# RS485.net
KiCad netlist of a schematic drawn in Altium Designer
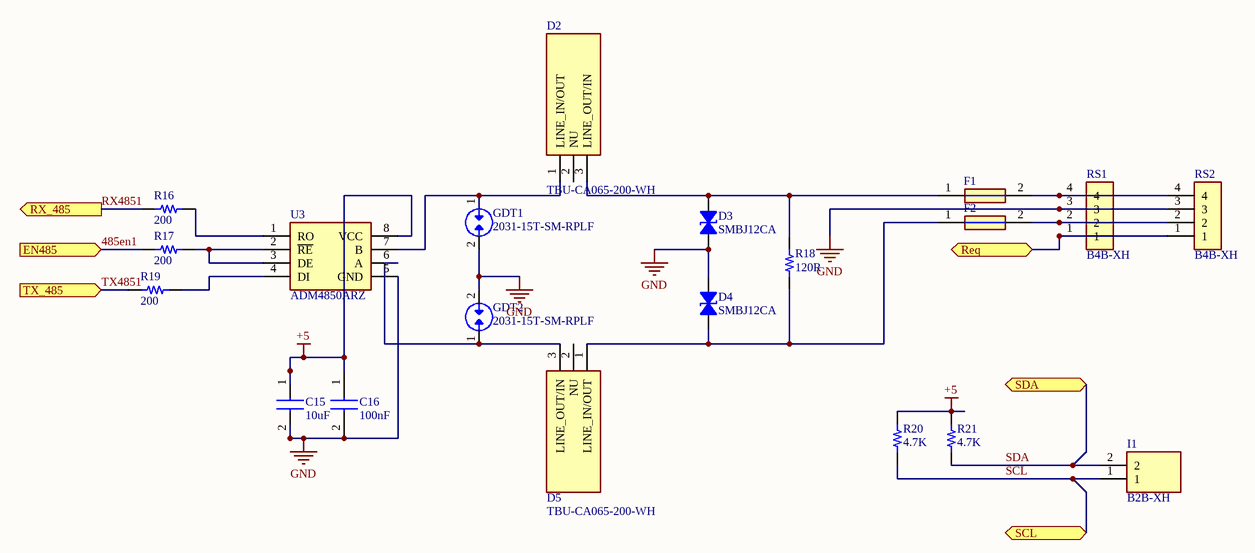
[diagram p0: RS485.SchDoc]

(export (version "E")
  (design (tool "Eeschema 10.0.6"))
  (components
    (comp (ref "C15")
      (value "10uF")
      (footprint "0603C")
      (description "CAP SMD 0603")
      (fields
        (field (name "MANUFACTURER_PART_NUMBER") "C1206C104Z5UACTU")
        (field (name "MOUSER PART NUMBER") "80-C1206C104Z5U")
      )
      (libsource (lib "*") (part "C1206C104Z5UACTU"))
    )
    (comp (ref "C16")
      (value "100nF")
      (footprint "0603C")
      (description "CAP SMD 0603")
      (fields
        (field (name "MANUFACTURER_PART_NUMBER") "C1206C104Z5UACTU")
        (field (name "MOUSER PART NUMBER") "80-C1206C104Z5U")
      )
      (libsource (lib "*") (part "C1206C104Z5UACTU"))
    )
    (comp (ref "D2")
      (value "TBU-CA065-200-WH")
      (footprint "TBUCA025050WH")
      (description "TVS Diode (Bi-directional)")
      (fields (field (name "MOUSER PART NUMBER") "652-TBU-CA065-200-WH"))
      (libsource (lib "") (part "TBU-CA065-200-WH_1"))
    )
    (comp (ref "D3")
      (value "SMBJ12CA")
      (footprint "DO214AA SMB")
      (description "TVS DIODE 12V 19.9V SMB")
      (fields (field (name "MANUFACTURER") "AVX Corporation"))
      (libsource (lib "Celestial Altium Library - altium_library") (part "Diode TVS"))
    )
    (comp (ref "D4")
      (value "SMBJ12CA")
      (footprint "DO214AA SMB")
      (description "TVS DIODE 12V 19.9V SMB")
      (fields (field (name "MANUFACTURER") "AVX Corporation"))
      (libsource (lib "Celestial Altium Library - altium_library") (part "Diode TVS"))
    )
    (comp (ref "D5")
      (value "TBU-CA065-200-WH")
      (footprint "TBUCA025050WH")
      (description "TVS Diode (Bi-directional)")
      (fields (field (name "MOUSER PART NUMBER") "652-TBU-CA065-200-WH"))
      (libsource (lib "*") (part "TBU-CA065-200-WH"))
    )
    (comp (ref "F1")
      (value "fuse 100mAmp")
      (footprint "1206 FUSE")
      (description "Fuse 1206")
      (fields (field (name "MANUFACTURER_PART_NUMBER") "1206SFS200F/63-2"))
      (libsource (lib "*") (part "1206SFS200F_63-2"))
    )
    (comp (ref "F2")
      (value "fuse 100mAmp")
      (footprint "1206 FUSE")
      (description "Fuse 1206")
      (fields (field (name "MANUFACTURER_PART_NUMBER") "1206SFS200F/63-2"))
      (libsource (lib "*") (part "1206SFS200F_63-2"))
    )
    (comp (ref "GDT1")
      (value "2031-15T-SM-RPLF")
      (footprint "TVS_2031-15T-SM-RPLF")
      (description "Gas Discharge Tube SMD")
      (libsource (lib "2031-15T-SM-RPLF") (part "2031-15T-SM-RPLF"))
    )
    (comp (ref "GDT2")
      (value "2031-15T-SM-RPLF")
      (footprint "TVS_2031-15T-SM-RPLF")
      (description "Gas Discharge Tube SMD")
      (libsource (lib "2031-15T-SM-RPLF") (part "2031-15T-SM-RPLF"))
    )
    (comp (ref "I1")
      (value "B2B-XH")
      (footprint "JST-B2B-XH")
      (description "XH 2pin standing")
      (libsource (lib "XHBBLIB") (part "B2B-XH"))
    )
    (comp (ref "R16")
      (value "200")
      (footprint "0603R")
      (description "RES SMD 0603")
      (fields (field (name "PART NUMBER") "CRCW080510K0JNEAIF") (field (name "MANUFACTURER") "Vishay Dale"))
      (libsource (lib "Celestial Altium Library - altium_library") (part "Resistor"))
    )
    (comp (ref "R17")
      (value "200")
      (footprint "0603R")
      (description "RES SMD 0603")
      (fields (field (name "PART NUMBER") "CRCW080510K0JNEAIF") (field (name "MANUFACTURER") "Vishay Dale"))
      (libsource (lib "Celestial Altium Library - altium_library") (part "Resistor"))
    )
    (comp (ref "R18")
      (value "120R")
      (footprint "0603R")
      (description "RES SMD 0603")
      (fields (field (name "PART NUMBER") "CRCW080510K0JNEAIF") (field (name "MANUFACTURER") "Vishay Dale"))
      (libsource (lib "Celestial Altium Library - altium_library") (part "Resistor"))
    )
    (comp (ref "R19")
      (value "200")
      (footprint "0603R")
      (description "RES SMD 0603")
      (fields (field (name "PART NUMBER") "CRCW080510K0JNEAIF") (field (name "MANUFACTURER") "Vishay Dale"))
      (libsource (lib "Celestial Altium Library - altium_library") (part "Resistor"))
    )
    (comp (ref "R20")
      (value "4.7K")
      (footprint "0603R")
      (description "RES SMD 0603")
      (fields (field (name "PART NUMBER") "CRCW080510K0JNEAIF") (field (name "MANUFACTURER") "Vishay Dale"))
      (libsource (lib "Celestial Altium Library - altium_library") (part "Resistor"))
    )
    (comp (ref "R21")
      (value "4.7K")
      (footprint "0603R")
      (description "RES SMD 0603")
      (fields (field (name "PART NUMBER") "CRCW080510K0JNEAIF") (field (name "MANUFACTURER") "Vishay Dale"))
      (libsource (lib "Celestial Altium Library - altium_library") (part "Resistor"))
    )
    (comp (ref "RS1")
      (value "B4B-XH")
      (footprint "JST-B4B-XH")
      (description "XH 4pin standing")
      (libsource (lib "XHBBLIB") (part "B4B-XH"))
    )
    (comp (ref "RS2")
      (value "B4B-XH")
      (footprint "JST-B4B-XH")
      (description "XH 4pin standing")
      (libsource (lib "XHBBLIB") (part "B4B-XH"))
    )
    (comp (ref "U3")
      (value "ADM4850ARZ")
      (footprint "SO8_N")
      (description "MAX485 SMD")
      (fields (field (name "MOUSER PART NUMBER") "584-ADM4850ARZ"))
      (libsource (lib "*") (part "ADM4850ARZ"))
    )
  )
  (nets
    (net (code "1") (name "+5") (class "Default")
      (node (ref "C15") (pin "1") (pinfunction "1_1") (pintype "passive"))
      (node (ref "C16") (pin "1") (pinfunction "1_1") (pintype "passive"))
      (node (ref "R20") (pin "1") (pinfunction "1_1") (pintype "passive"))
      (node (ref "R21") (pin "1") (pinfunction "1_1") (pintype "passive"))
      (node (ref "U3") (pin "8") (pinfunction "VCC_8") (pintype "passive"))
    )
    (net (code "2") (name "/485en1") (class "Default")
      (node (ref "R17") (pin "2") (pinfunction "2_2") (pintype "passive"))
    )
    (net (code "3") (name "/RX4851") (class "Default")
      (node (ref "R16") (pin "2") (pinfunction "2_2") (pintype "passive"))
    )
    (net (code "4") (name "/Req") (class "Default")
      (node (ref "RS1") (pin "1") (pinfunction "1_1") (pintype "passive"))
      (node (ref "RS2") (pin "1") (pinfunction "1_1") (pintype "passive"))
    )
    (net (code "5") (name "/SCL") (class "Default")
      (node (ref "I1") (pin "1") (pinfunction "1_1") (pintype "passive"))
      (node (ref "R20") (pin "2") (pinfunction "2_2") (pintype "passive"))
    )
    (net (code "6") (name "/SDA") (class "Default")
      (node (ref "I1") (pin "2") (pinfunction "2_2") (pintype "passive"))
      (node (ref "R21") (pin "2") (pinfunction "2_2") (pintype "passive"))
    )
    (net (code "7") (name "/TX4851") (class "Default")
      (node (ref "R19") (pin "2") (pinfunction "2_2") (pintype "passive"))
    )
    (net (code "8") (name "GND") (class "Default")
      (node (ref "C15") (pin "2") (pinfunction "2_2") (pintype "passive"))
      (node (ref "C16") (pin "2") (pinfunction "2_2") (pintype "passive"))
      (node (ref "D3") (pin "1") (pinfunction "1_1") (pintype "passive"))
      (node (ref "D4") (pin "2") (pinfunction "2_2") (pintype "passive"))
      (node (ref "GDT1") (pin "2") (pinfunction "2_2") (pintype "passive"))
      (node (ref "GDT2") (pin "2") (pinfunction "2_2") (pintype "passive"))
      (node (ref "RS1") (pin "3") (pinfunction "3_3") (pintype "passive"))
      (node (ref "RS2") (pin "3") (pinfunction "3_3") (pintype "passive"))
      (node (ref "U3") (pin "5") (pinfunction "GND_5") (pintype "passive"))
    )
    (net (code "9") (name "Net-(D2-LINE_IN{slash}OUT)") (class "Default")
      (node (ref "D2") (pin "1") (pinfunction "LINE_IN/OUT_1") (pintype "passive"))
      (node (ref "GDT1") (pin "1") (pinfunction "1_1") (pintype "passive"))
      (node (ref "U3") (pin "7") (pinfunction "B_7") (pintype "passive"))
    )
    (net (code "10") (name "Net-(D2-LINE_OUT{slash}IN)") (class "Default")
      (node (ref "D2") (pin "3") (pinfunction "LINE_OUT/IN_3") (pintype "passive"))
      (node (ref "D3") (pin "2") (pinfunction "2_2") (pintype "passive"))
      (node (ref "F1") (pin "1") (pinfunction "1_1") (pintype "passive"))
      (node (ref "R18") (pin "1") (pinfunction "1_1") (pintype "passive"))
    )
    (net (code "11") (name "Net-(D5-LINE_IN{slash}OUT)") (class "Default")
      (node (ref "D4") (pin "1") (pinfunction "1_1") (pintype "passive"))
      (node (ref "D5") (pin "1") (pinfunction "LINE_IN/OUT_1") (pintype "passive"))
      (node (ref "F2") (pin "1") (pinfunction "1_1") (pintype "passive"))
      (node (ref "R18") (pin "2") (pinfunction "2_2") (pintype "passive"))
    )
    (net (code "12") (name "Net-(D5-LINE_OUT{slash}IN)") (class "Default")
      (node (ref "D5") (pin "3") (pinfunction "LINE_OUT/IN_3") (pintype "passive"))
      (node (ref "GDT2") (pin "1") (pinfunction "1_1") (pintype "passive"))
      (node (ref "U3") (pin "6") (pinfunction "A_6") (pintype "passive"))
    )
    (net (code "13") (name "Net-(F1-Pad2)") (class "Default")
      (node (ref "F1") (pin "2") (pinfunction "2_2") (pintype "passive"))
      (node (ref "RS1") (pin "4") (pinfunction "4_4") (pintype "passive"))
      (node (ref "RS2") (pin "4") (pinfunction "4_4") (pintype "passive"))
    )
    (net (code "14") (name "Net-(F2-Pad2)") (class "Default")
      (node (ref "F2") (pin "2") (pinfunction "2_2") (pintype "passive"))
      (node (ref "RS1") (pin "2") (pinfunction "2_2") (pintype "passive"))
      (node (ref "RS2") (pin "2") (pinfunction "2_2") (pintype "passive"))
    )
    (net (code "15") (name "Net-(U3-DE)") (class "Default")
      (node (ref "R17") (pin "1") (pinfunction "1_1") (pintype "passive"))
      (node (ref "U3") (pin "2") (pinfunction "~{RE}_2") (pintype "passive"))
      (node (ref "U3") (pin "3") (pinfunction "DE_3") (pintype "passive"))
    )
    (net (code "16") (name "Net-(U3-DI)") (class "Default")
      (node (ref "R19") (pin "1") (pinfunction "1_1") (pintype "passive"))
      (node (ref "U3") (pin "4") (pinfunction "DI_4") (pintype "passive"))
    )
    (net (code "17") (name "Net-(U3-RO)") (class "Default")
      (node (ref "R16") (pin "1") (pinfunction "1_1") (pintype "passive"))
      (node (ref "U3") (pin "1") (pinfunction "RO_1") (pintype "passive"))
    )
    (net (code "18") (name "unconnected-(D2-NU-Pad2)") (class "Default")
      (node (ref "D2") (pin "2") (pinfunction "NU_2") (pintype "passive"))
    )
    (net (code "19") (name "unconnected-(D5-NU-Pad2)") (class "Default")
      (node (ref "D5") (pin "2") (pinfunction "NU_2") (pintype "passive"))
    )
  )
)
